# NAPaC_DetachableModule.net
KiCad netlist of a schematic drawn in Altium Designer
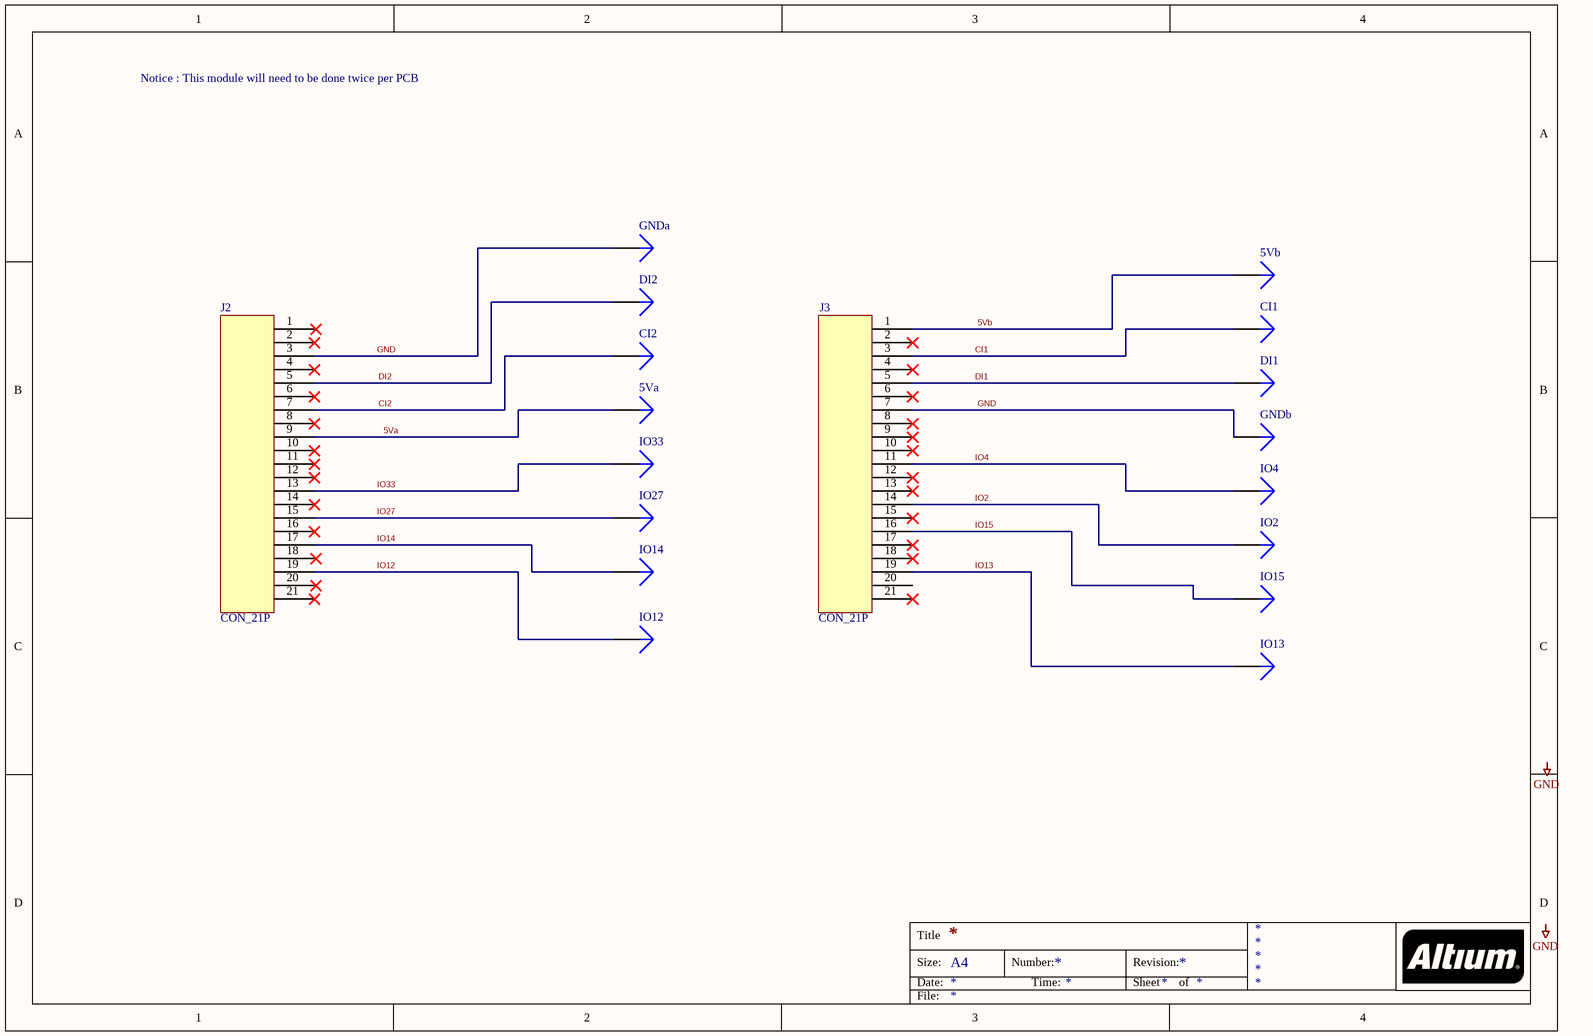
[diagram p0: NAPaC_DetachableModule.SchDoc]

(export (version "E")
  (design (tool "Eeschema 10.0.6"))
  (components
    (comp (ref "5Va")
      (value "Plug")
      (footprint "PIN_1")
      (fields (field (name "PUBLISHER") "Altium Limited"))
      (libsource (lib "Miscellaneous Connectors") (part "Plug"))
    )
    (comp (ref "5Vb")
      (value "Plug")
      (footprint "PIN_1")
      (fields (field (name "PUBLISHER") "Altium Limited"))
      (libsource (lib "Miscellaneous Connectors") (part "Plug"))
    )
    (comp (ref "CI1")
      (value "Plug")
      (footprint "PIN_1")
      (fields (field (name "PUBLISHER") "Altium Limited"))
      (libsource (lib "Miscellaneous Connectors") (part "Plug"))
    )
    (comp (ref "CI2")
      (value "Plug")
      (footprint "PIN_1")
      (fields (field (name "PUBLISHER") "Altium Limited"))
      (libsource (lib "Miscellaneous Connectors") (part "Plug"))
    )
    (comp (ref "DI1")
      (value "Plug")
      (footprint "PIN_1")
      (fields (field (name "PUBLISHER") "Altium Limited"))
      (libsource (lib "Miscellaneous Connectors") (part "Plug"))
    )
    (comp (ref "DI2")
      (value "Plug")
      (footprint "PIN_1")
      (fields (field (name "PUBLISHER") "Altium Limited"))
      (libsource (lib "Miscellaneous Connectors") (part "Plug"))
    )
    (comp (ref "GNDa")
      (value "Plug")
      (footprint "PIN_1")
      (fields (field (name "PUBLISHER") "Altium Limited"))
      (libsource (lib "Miscellaneous Connectors") (part "Plug"))
    )
    (comp (ref "GNDb")
      (value "Plug")
      (footprint "PIN_1")
      (fields (field (name "PUBLISHER") "Altium Limited"))
      (libsource (lib "Miscellaneous Connectors") (part "Plug"))
    )
    (comp (ref "IO2")
      (value "Plug")
      (footprint "PIN_1")
      (fields (field (name "PUBLISHER") "Altium Limited"))
      (libsource (lib "Miscellaneous Connectors") (part "Plug"))
    )
    (comp (ref "IO4")
      (value "Plug")
      (footprint "PIN_1")
      (fields (field (name "PUBLISHER") "Altium Limited"))
      (libsource (lib "Miscellaneous Connectors") (part "Plug"))
    )
    (comp (ref "IO12")
      (value "Plug")
      (footprint "PIN_1")
      (fields (field (name "PUBLISHER") "Altium Limited"))
      (libsource (lib "Miscellaneous Connectors") (part "Plug"))
    )
    (comp (ref "IO13")
      (value "Plug")
      (footprint "PIN_1")
      (fields (field (name "PUBLISHER") "Altium Limited"))
      (libsource (lib "Miscellaneous Connectors") (part "Plug"))
    )
    (comp (ref "IO14")
      (value "Plug")
      (footprint "PIN_1")
      (fields (field (name "PUBLISHER") "Altium Limited"))
      (libsource (lib "Miscellaneous Connectors") (part "Plug"))
    )
    (comp (ref "IO15")
      (value "Plug")
      (footprint "PIN_1")
      (fields (field (name "PUBLISHER") "Altium Limited"))
      (libsource (lib "Miscellaneous Connectors") (part "Plug"))
    )
    (comp (ref "IO27")
      (value "Plug")
      (footprint "PIN_1")
      (fields (field (name "PUBLISHER") "Altium Limited"))
      (libsource (lib "Miscellaneous Connectors") (part "Plug"))
    )
    (comp (ref "IO33")
      (value "Plug")
      (footprint "PIN_1")
      (fields (field (name "PUBLISHER") "Altium Limited"))
      (libsource (lib "Miscellaneous Connectors") (part "Plug"))
    )
    (comp (ref "J2")
      (value "CON_21P")
      (footprint "PINS_HEADER-21")
      (description "21 Positions Header, Breakaway Connector 0.100\" (2.54mm) Through Hole Tin")
      (libsource (lib "NAPaC_Schlib") (part "PINS_HEADER"))
    )
    (comp (ref "J3")
      (value "CON_21P")
      (footprint "PINS_HEADER-21")
      (description "21 Positions Header, Breakaway Connector 0.100\" (2.54mm) Through Hole Tin")
      (libsource (lib "NAPaC_Schlib") (part "PINS_HEADER"))
    )
  )
  (nets
    (net (code "1") (name "/5Va") (class "Default")
      (node (ref "5Va") (pin "1") (pinfunction "1_1") (pintype "passive"))
      (node (ref "J2") (pin "9") (pinfunction "1_9") (pintype "passive"))
    )
    (net (code "2") (name "/5Vb") (class "Default")
      (node (ref "5Vb") (pin "1") (pinfunction "1_1") (pintype "passive"))
      (node (ref "J3") (pin "1") (pinfunction "1_1") (pintype "passive"))
    )
    (net (code "3") (name "/CI1") (class "Default")
      (node (ref "CI1") (pin "1") (pinfunction "1_1") (pintype "passive"))
      (node (ref "J3") (pin "3") (pinfunction "1_3") (pintype "passive"))
    )
    (net (code "4") (name "/CI2") (class "Default")
      (node (ref "CI2") (pin "1") (pinfunction "1_1") (pintype "passive"))
      (node (ref "J2") (pin "7") (pinfunction "1_7") (pintype "passive"))
    )
    (net (code "5") (name "/DI1") (class "Default")
      (node (ref "DI1") (pin "1") (pinfunction "1_1") (pintype "passive"))
      (node (ref "J3") (pin "5") (pinfunction "1_5") (pintype "passive"))
    )
    (net (code "6") (name "/DI2") (class "Default")
      (node (ref "DI2") (pin "1") (pinfunction "1_1") (pintype "passive"))
      (node (ref "J2") (pin "5") (pinfunction "1_5") (pintype "passive"))
    )
    (net (code "7") (name "/IO2") (class "Default")
      (node (ref "IO2") (pin "1") (pinfunction "1_1") (pintype "passive"))
      (node (ref "J3") (pin "14") (pinfunction "1_14") (pintype "passive"))
    )
    (net (code "8") (name "/IO4") (class "Default")
      (node (ref "IO4") (pin "1") (pinfunction "1_1") (pintype "passive"))
      (node (ref "J3") (pin "11") (pinfunction "1_11") (pintype "passive"))
    )
    (net (code "9") (name "/IO12") (class "Default")
      (node (ref "IO12") (pin "1") (pinfunction "1_1") (pintype "passive"))
      (node (ref "J2") (pin "19") (pinfunction "1_19") (pintype "passive"))
    )
    (net (code "10") (name "/IO13") (class "Default")
      (node (ref "IO13") (pin "1") (pinfunction "1_1") (pintype "passive"))
      (node (ref "J3") (pin "19") (pinfunction "1_19") (pintype "passive"))
    )
    (net (code "11") (name "/IO14") (class "Default")
      (node (ref "IO14") (pin "1") (pinfunction "1_1") (pintype "passive"))
      (node (ref "J2") (pin "17") (pinfunction "1_17") (pintype "passive"))
    )
    (net (code "12") (name "/IO15") (class "Default")
      (node (ref "IO15") (pin "1") (pinfunction "1_1") (pintype "passive"))
      (node (ref "J3") (pin "16") (pinfunction "1_16") (pintype "passive"))
    )
    (net (code "13") (name "/IO27") (class "Default")
      (node (ref "IO27") (pin "1") (pinfunction "1_1") (pintype "passive"))
      (node (ref "J2") (pin "15") (pinfunction "1_15") (pintype "passive"))
    )
    (net (code "14") (name "/IO33") (class "Default")
      (node (ref "IO33") (pin "1") (pinfunction "1_1") (pintype "passive"))
      (node (ref "J2") (pin "13") (pinfunction "1_13") (pintype "passive"))
    )
    (net (code "15") (name "GND") (class "Default")
      (node (ref "GNDa") (pin "1") (pinfunction "1_1") (pintype "passive"))
      (node (ref "GNDb") (pin "1") (pinfunction "1_1") (pintype "passive"))
      (node (ref "J2") (pin "3") (pinfunction "1_3") (pintype "passive"))
      (node (ref "J3") (pin "7") (pinfunction "1_7") (pintype "passive"))
    )
    (net (code "16") (name "unconnected-(J2-1-Pad2)") (class "Default")
      (node (ref "J2") (pin "2") (pinfunction "1_2") (pintype "passive+no_connect"))
    )
    (net (code "17") (name "unconnected-(J2-1-Pad4)") (class "Default")
      (node (ref "J2") (pin "4") (pinfunction "1_4") (pintype "passive+no_connect"))
    )
    (net (code "18") (name "unconnected-(J2-1-Pad6)") (class "Default")
      (node (ref "J2") (pin "6") (pinfunction "1_6") (pintype "passive+no_connect"))
    )
    (net (code "19") (name "unconnected-(J2-1-Pad8)") (class "Default")
      (node (ref "J2") (pin "8") (pinfunction "1_8") (pintype "passive+no_connect"))
    )
    (net (code "20") (name "unconnected-(J2-1-Pad10)") (class "Default")
      (node (ref "J2") (pin "10") (pinfunction "1_10") (pintype "passive+no_connect"))
    )
    (net (code "21") (name "unconnected-(J2-1-Pad11)") (class "Default")
      (node (ref "J2") (pin "11") (pinfunction "1_11") (pintype "passive+no_connect"))
    )
    (net (code "22") (name "unconnected-(J2-1-Pad12)") (class "Default")
      (node (ref "J2") (pin "12") (pinfunction "1_12") (pintype "passive+no_connect"))
    )
    (net (code "23") (name "unconnected-(J2-1-Pad14)") (class "Default")
      (node (ref "J2") (pin "14") (pinfunction "1_14") (pintype "passive+no_connect"))
    )
    (net (code "24") (name "unconnected-(J2-1-Pad16)") (class "Default")
      (node (ref "J2") (pin "16") (pinfunction "1_16") (pintype "passive+no_connect"))
    )
    (net (code "25") (name "unconnected-(J2-1-Pad18)") (class "Default")
      (node (ref "J2") (pin "18") (pinfunction "1_18") (pintype "passive"))
    )
    (net (code "26") (name "unconnected-(J2-1-Pad20)") (class "Default")
      (node (ref "J2") (pin "20") (pinfunction "1_20") (pintype "passive"))
    )
    (net (code "27") (name "unconnected-(J2-1-Pad21)") (class "Default")
      (node (ref "J2") (pin "21") (pinfunction "1_21") (pintype "passive+no_connect"))
    )
    (net (code "28") (name "unconnected-(J2-Pad1)") (class "Default")
      (node (ref "J2") (pin "1") (pinfunction "1_1") (pintype "passive"))
    )
    (net (code "29") (name "unconnected-(J3-1-Pad2)") (class "Default")
      (node (ref "J3") (pin "2") (pinfunction "1_2") (pintype "passive+no_connect"))
    )
    (net (code "30") (name "unconnected-(J3-1-Pad4)") (class "Default")
      (node (ref "J3") (pin "4") (pinfunction "1_4") (pintype "passive+no_connect"))
    )
    (net (code "31") (name "unconnected-(J3-1-Pad6)") (class "Default")
      (node (ref "J3") (pin "6") (pinfunction "1_6") (pintype "passive+no_connect"))
    )
    (net (code "32") (name "unconnected-(J3-1-Pad8)") (class "Default")
      (node (ref "J3") (pin "8") (pinfunction "1_8") (pintype "passive+no_connect"))
    )
    (net (code "33") (name "unconnected-(J3-1-Pad9)") (class "Default")
      (node (ref "J3") (pin "9") (pinfunction "1_9") (pintype "passive+no_connect"))
    )
    (net (code "34") (name "unconnected-(J3-1-Pad10)") (class "Default")
      (node (ref "J3") (pin "10") (pinfunction "1_10") (pintype "passive+no_connect"))
    )
    (net (code "35") (name "unconnected-(J3-1-Pad12)") (class "Default")
      (node (ref "J3") (pin "12") (pinfunction "1_12") (pintype "passive+no_connect"))
    )
    (net (code "36") (name "unconnected-(J3-1-Pad13)") (class "Default")
      (node (ref "J3") (pin "13") (pinfunction "1_13") (pintype "passive+no_connect"))
    )
    (net (code "37") (name "unconnected-(J3-1-Pad15)") (class "Default")
      (node (ref "J3") (pin "15") (pinfunction "1_15") (pintype "passive+no_connect"))
    )
    (net (code "38") (name "unconnected-(J3-1-Pad17)") (class "Default")
      (node (ref "J3") (pin "17") (pinfunction "1_17") (pintype "passive+no_connect"))
    )
    (net (code "39") (name "unconnected-(J3-1-Pad18)") (class "Default")
      (node (ref "J3") (pin "18") (pinfunction "1_18") (pintype "passive+no_connect"))
    )
    (net (code "40") (name "unconnected-(J3-1-Pad20)") (class "Default")
      (node (ref "J3") (pin "20") (pinfunction "1_20") (pintype "passive"))
    )
    (net (code "41") (name "unconnected-(J3-1-Pad21)") (class "Default")
      (node (ref "J3") (pin "21") (pinfunction "1_21") (pintype "passive+no_connect"))
    )
  )
)
